# IEEE-802_15_4.net
KiCad netlist of a schematic drawn in Altium Designer
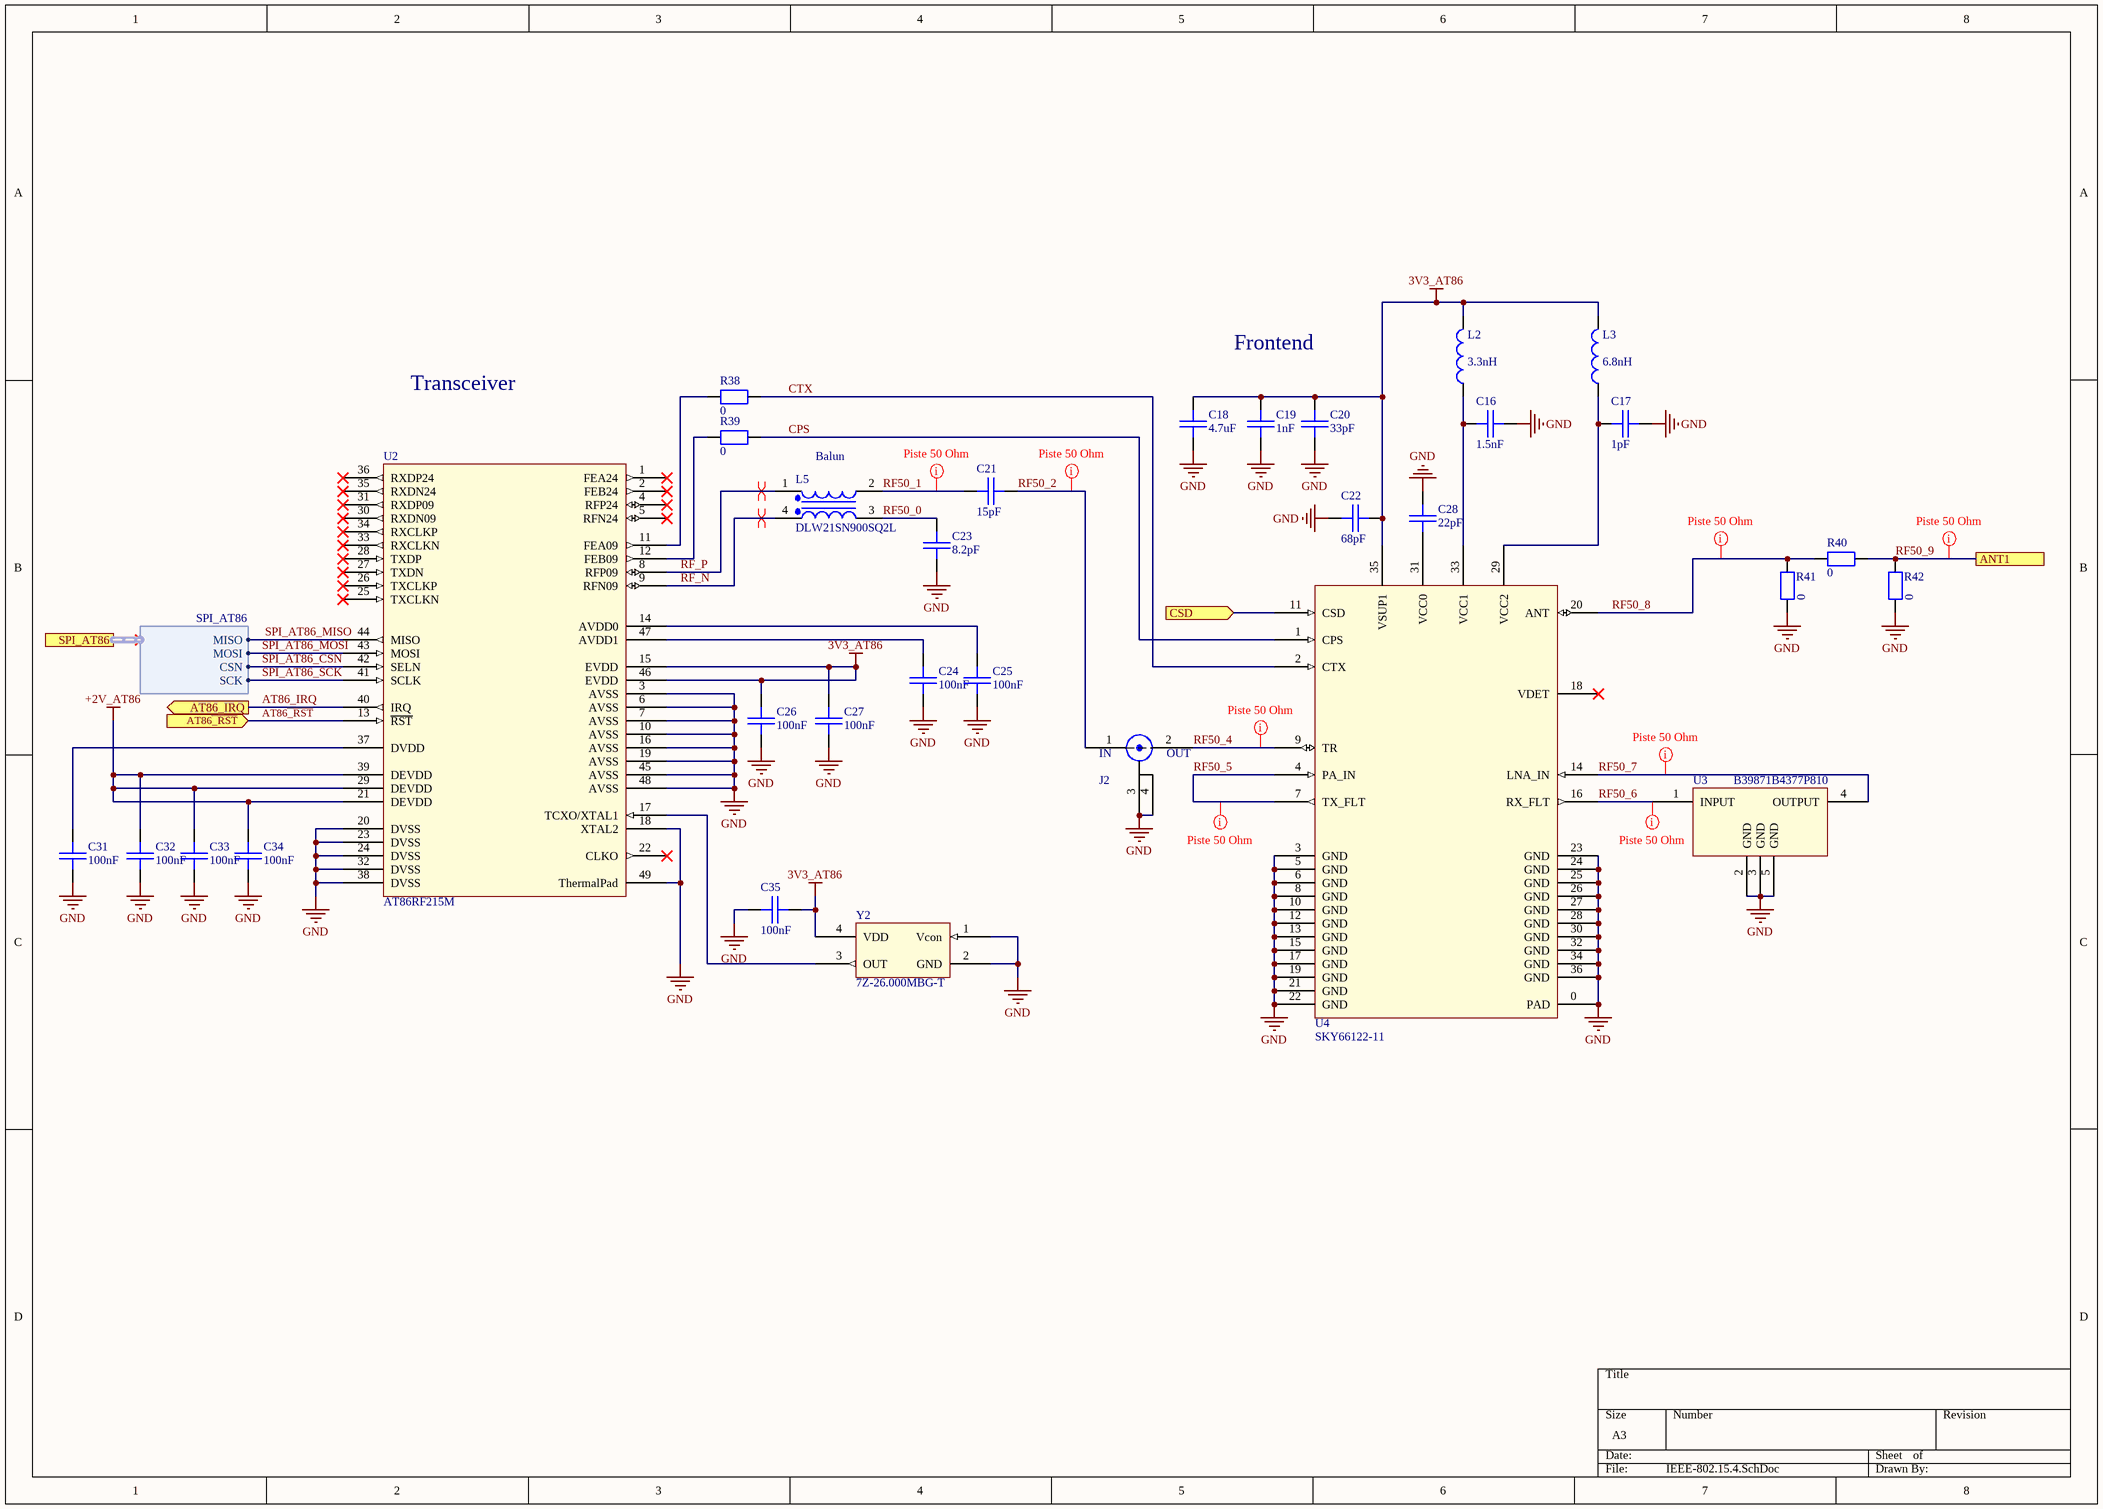
[diagram p0: IEEE-802.15.4.SchDoc]

(export (version "E")
  (design (tool "Eeschema 10.0.6"))
  (components
    (comp (ref "C16")
      (value "1.5nF")
      (footprint "SM/C_0402")
      (fields (field (name "Comment") "C-1nF-0402"))
      (libsource (lib "IEEE-802.15.4") (part "C-1.5nF-0402"))
    )
    (comp (ref "C17")
      (value "1pF")
      (footprint "SM/C_0402")
      (fields (field (name "Comment") "C-1pF-0402"))
      (libsource (lib "IEEE-802.15.4") (part "C-1pF-0402"))
    )
    (comp (ref "C18")
      (value "4.7uF")
      (footprint "SM/C_0603")
      (fields
        (field (name "VOLTAGE") "6.3V")
        (field (name "TOLERANCE") "10%")
        (field (name "Comment") "C-4.7uF-0603")
      )
      (libsource (lib "IEEE-802.15.4") (part "C-4.7uF-0603"))
    )
    (comp (ref "C19")
      (value "1nF")
      (footprint "SM/C_0402")
      (fields
        (field (name "VOLTAGE") "50V")
        (field (name "TOLERANCE") "1%")
        (field (name "Comment") "C-1nF-0402")
      )
      (libsource (lib "IEEE-802.15.4") (part "C-1nF-0402"))
    )
    (comp (ref "C20")
      (value "33pF")
      (footprint "SM/C_0402")
      (fields
        (field (name "VOLTAGE") "50V")
        (field (name "TOLERANCE") "5%")
        (field (name "Comment") "C-33pF-0402")
      )
      (libsource (lib "IEEE-802.15.4") (part "C-33pF-0402"))
    )
    (comp (ref "C21")
      (value "15pF")
      (footprint "TB_Module_RF_OFDM:SM/C_0402")
      (fields
        (field (name "VOLTAGE") "6.3V")
        (field (name "TOLERANCE") "10%")
        (field (name "Comment") "C-15pF-0402")
      )
      (libsource (lib "TB_Module_RF_OFDM") (part "C-15pF-0402"))
    )
    (comp (ref "C22")
      (value "68pF")
      (footprint "SM/C_0402")
      (fields
        (field (name "VOLTAGE") "50V")
        (field (name "TOLERANCE") "5%")
        (field (name "Comment") "C-68pF-0402")
      )
      (libsource (lib "IEEE-802.15.4") (part "C-68pF-0402"))
    )
    (comp (ref "C23")
      (value "8.2pF")
      (footprint "TB_Module_RF_OFDM:SM/C_0402")
      (fields
        (field (name "VOLTAGE") "6.3V")
        (field (name "TOLERANCE") "10%")
        (field (name "Comment") "C-8.2pF-0402")
      )
      (libsource (lib "TB_Module_RF_OFDM") (part "C-8.2pF-0402"))
    )
    (comp (ref "C24")
      (value "100nF")
      (footprint "TB_Module_RF_OFDM:SM/C_0402")
      (fields
        (field (name "VOLTAGE") "25V")
        (field (name "TOLERANCE") "10%")
        (field (name "Comment") "C-100nF-0402")
      )
      (libsource (lib "TB_Module_RF_OFDM") (part "C-100nF-0402"))
    )
    (comp (ref "C25")
      (value "100nF")
      (footprint "TB_Module_RF_OFDM:SM/C_0402")
      (fields
        (field (name "VOLTAGE") "25V")
        (field (name "TOLERANCE") "10%")
        (field (name "Comment") "C-100nF-0402")
      )
      (libsource (lib "TB_Module_RF_OFDM") (part "C-100nF-0402"))
    )
    (comp (ref "C26")
      (value "100nF")
      (footprint "TB_Module_RF_OFDM:SM/C_0402")
      (fields
        (field (name "VOLTAGE") "25V")
        (field (name "TOLERANCE") "10%")
        (field (name "Comment") "C-100nF-0402")
      )
      (libsource (lib "TB_Module_RF_OFDM") (part "C-100nF-0402"))
    )
    (comp (ref "C27")
      (value "100nF")
      (footprint "TB_Module_RF_OFDM:SM/C_0402")
      (fields
        (field (name "VOLTAGE") "25V")
        (field (name "TOLERANCE") "10%")
        (field (name "Comment") "C-100nF-0402")
      )
      (libsource (lib "TB_Module_RF_OFDM") (part "C-100nF-0402"))
    )
    (comp (ref "C28")
      (value "22pF")
      (footprint "SM/C_0402")
      (fields
        (field (name "VOLTAGE") "50V")
        (field (name "TOLERANCE") "1%")
        (field (name "Comment") "C-22pF-0402")
      )
      (libsource (lib "IEEE-802.15.4") (part "C-22pF-0402"))
    )
    (comp (ref "C31")
      (value "100nF")
      (footprint "TB_Module_RF_OFDM:SM/C_0402")
      (fields
        (field (name "VOLTAGE") "25V")
        (field (name "TOLERANCE") "10%")
        (field (name "Comment") "C-100nF-0402")
      )
      (libsource (lib "TB_Module_RF_OFDM") (part "C-100nF-0402"))
    )
    (comp (ref "C32")
      (value "100nF")
      (footprint "TB_Module_RF_OFDM:SM/C_0402")
      (fields
        (field (name "VOLTAGE") "25V")
        (field (name "TOLERANCE") "10%")
        (field (name "Comment") "C-100nF-0402")
      )
      (libsource (lib "TB_Module_RF_OFDM") (part "C-100nF-0402"))
    )
    (comp (ref "C33")
      (value "100nF")
      (footprint "TB_Module_RF_OFDM:SM/C_0402")
      (fields
        (field (name "VOLTAGE") "25V")
        (field (name "TOLERANCE") "10%")
        (field (name "Comment") "C-100nF-0402")
      )
      (libsource (lib "TB_Module_RF_OFDM") (part "C-100nF-0402"))
    )
    (comp (ref "C34")
      (value "100nF")
      (footprint "TB_Module_RF_OFDM:SM/C_0402")
      (fields
        (field (name "VOLTAGE") "25V")
        (field (name "TOLERANCE") "10%")
        (field (name "Comment") "C-100nF-0402")
      )
      (libsource (lib "TB_Module_RF_OFDM") (part "C-100nF-0402"))
    )
    (comp (ref "C35")
      (value "100nF")
      (footprint "TB_Module_RF_OFDM:SM/C_0402")
      (fields
        (field (name "VOLTAGE") "25V")
        (field (name "TOLERANCE") "10%")
        (field (name "Comment") "C-100nF-0402")
      )
      (libsource (lib "TB_Module_RF_OFDM") (part "C-100nF-0402"))
    )
    (comp (ref "J2")
      (value "MM8930-2620RJ4")
      (footprint "MM8030-2610RJ3")
      (description "SWG Connecteur Socle, prise femelle 50Ohms")
      (libsource (lib "IEEE-802.15.4") (part "MM8030-2610RJ3"))
    )
    (comp (ref "L2")
      (value "3.3nH")
      (footprint "SM/L_0402")
      (fields (field (name "TOLERANCE") "0.3nH") (field (name "Comment") "L-3.3nH-0402"))
      (libsource (lib "IEEE-802.15.4") (part "L-3.3nH-0402"))
    )
    (comp (ref "L3")
      (value "6.8nH")
      (footprint "SM/L_0603 (1608)")
      (fields (field (name "TOLERANCE") "5%") (field (name "Comment") "L-6.8nH-0603"))
      (libsource (lib "IEEE-802.15.4") (part "L-6.8nH-0603"))
    )
    (comp (ref "L5")
      (value "DLW21SN900SQ2L")
      (footprint "MURA-DLW21SN900SQ2L-4_V")
      (description "Chip Common Mode Choke Coil, 90 Ohm, 330 mA, -40 to 85 degC, 4-Pin SMD, RoHS, Tape and Reel")
      (fields (field (name "MANUFACTURER") "Murata"))
      (libsource (lib "TB_Module_RF_OFDM") (part "DLW21SN900SQ2L"))
    )
    (comp (ref "R38")
      (value "0")
      (footprint "SM/R_0402")
      (fields (field (name "TOLERANCE") "1%") (field (name "Comment") "R-0-0402"))
      (libsource (lib "TB_Module_RF_OFDM") (part "R-0-0402"))
    )
    (comp (ref "R39")
      (value "0")
      (footprint "SM/R_0402")
      (fields (field (name "TOLERANCE") "1%") (field (name "Comment") "R-0-0402"))
      (libsource (lib "TB_Module_RF_OFDM") (part "R-0-0402"))
    )
    (comp (ref "R40")
      (value "0")
      (footprint "SM/R_0402")
      (fields (field (name "TOLERANCE") "1%") (field (name "Comment") "R-0-0402"))
      (libsource (lib "TB_Module_RF_OFDM") (part "R-0-0402"))
    )
    (comp (ref "R41")
      (value "0")
      (footprint "SM/R_0402")
      (fields (field (name "TOLERANCE") "1%") (field (name "Comment") "R-0-0402"))
      (libsource (lib "TB_Module_RF_OFDM") (part "R-0-0402"))
    )
    (comp (ref "R42")
      (value "0")
      (footprint "SM/R_0402")
      (fields (field (name "TOLERANCE") "1%") (field (name "Comment") "R-0-0402"))
      (libsource (lib "TB_Module_RF_OFDM") (part "R-0-0402"))
    )
    (comp (ref "U2")
      (value "AT86RF215M")
      (footprint "QFN50P700X700X90-49N-D")
      (description "IC RF TXRX 802.15.4/ISM 48-VFQFN")
      (libsource (lib "TB_Module_RF_OFDM") (part "AT86RF215M"))
    )
    (comp (ref "U3")
      (value "B39871B4377P810")
      (footprint "B39871B4377P810")
      (libsource (lib "IEEE-802.15.4") (part "B39871B4377P810"))
    )
    (comp (ref "U4")
      (value "SKY66122-11")
      (footprint "SKY66122-11")
      (libsource (lib "IEEE-802.15.4") (part "SKY66122-11"))
    )
    (comp (ref "Y2")
      (value "7Z-26.000MBG-T")
      (footprint "TCXO")
      (description "XTAL OSC TCXO 26.0000MHZ SNWV")
      (libsource (lib "IEEE-802.15.4") (part "7Z-26.000MBG-T"))
    )
  )
  (nets
    (net (code "2") (name "+2V_AT86") (class "Default")
      (node (ref "C32") (pin "2") (pinfunction "2_2") (pintype "passive"))
      (node (ref "C33") (pin "2") (pinfunction "2_2") (pintype "passive"))
      (node (ref "C34") (pin "2") (pinfunction "2_2") (pintype "passive"))
      (node (ref "U2") (pin "21") (pinfunction "DEVDD_21") (pintype "power_in"))
      (node (ref "U2") (pin "29") (pinfunction "DEVDD_29") (pintype "power_in"))
      (node (ref "U2") (pin "39") (pinfunction "DEVDD_39") (pintype "power_in"))
    )
    (net (code "3") (name "/AT86_IRQ") (class "Default")
      (node (ref "U2") (pin "40") (pinfunction "IRQ_40") (pintype "output"))
    )
    (net (code "4") (name "/AT86~{_RST}") (class "Default")
      (node (ref "U2") (pin "13") (pinfunction "~{RST}_13") (pintype "input"))
    )
    (net (code "5") (name "/CPS") (class "Default")
      (node (ref "R39") (pin "2") (pinfunction "2_2") (pintype "passive"))
      (node (ref "U4") (pin "1") (pinfunction "CPS_1") (pintype "input"))
    )
    (net (code "6") (name "/CSD") (class "Default")
      (node (ref "U4") (pin "11") (pinfunction "CSD_11") (pintype "input"))
    )
    (net (code "7") (name "/CTX") (class "Default")
      (node (ref "R38") (pin "2") (pinfunction "2_2") (pintype "passive"))
      (node (ref "U4") (pin "2") (pinfunction "CTX_2") (pintype "input"))
    )
    (net (code "8") (name "/RF50_0") (class "Default")
      (node (ref "C23") (pin "2") (pinfunction "2_2") (pintype "passive"))
      (node (ref "L5") (pin "3") (pinfunction "3_3") (pintype "passive"))
    )
    (net (code "9") (name "/RF50_1") (class "Default")
      (node (ref "C21") (pin "1") (pinfunction "1_1") (pintype "passive"))
      (node (ref "L5") (pin "2") (pinfunction "2_2") (pintype "passive"))
    )
    (net (code "10") (name "/RF50_2") (class "Default")
      (node (ref "C21") (pin "2") (pinfunction "2_2") (pintype "passive"))
      (node (ref "J2") (pin "1") (pinfunction "IN_1") (pintype "passive"))
    )
    (net (code "11") (name "/RF50_4") (class "Default")
      (node (ref "J2") (pin "2") (pinfunction "IN_2") (pintype "passive"))
      (node (ref "U4") (pin "9") (pinfunction "TR_9") (pintype "bidirectional"))
    )
    (net (code "12") (name "/RF50_5") (class "Default")
      (node (ref "U4") (pin "4") (pinfunction "PA_IN_4") (pintype "input"))
      (node (ref "U4") (pin "7") (pinfunction "TX_FLT_7") (pintype "output"))
    )
    (net (code "13") (name "/RF50_6") (class "Default")
      (node (ref "U3") (pin "1") (pinfunction "INPUT_1") (pintype "passive"))
      (node (ref "U4") (pin "16") (pinfunction "RX_FLT_16") (pintype "output"))
    )
    (net (code "14") (name "/RF50_7") (class "Default")
      (node (ref "U3") (pin "4") (pinfunction "OUTPUT_4") (pintype "passive"))
      (node (ref "U4") (pin "14") (pinfunction "LNA_IN_14") (pintype "input"))
    )
    (net (code "15") (name "/RF50_8") (class "Default")
      (node (ref "R40") (pin "1") (pinfunction "1_1") (pintype "passive"))
      (node (ref "R41") (pin "2") (pinfunction "2_2") (pintype "passive"))
      (node (ref "U4") (pin "20") (pinfunction "ANT_20") (pintype "bidirectional"))
    )
    (net (code "16") (name "/RF50_9") (class "Default")
      (node (ref "R40") (pin "2") (pinfunction "2_2") (pintype "passive"))
      (node (ref "R42") (pin "2") (pinfunction "2_2") (pintype "passive"))
    )
    (net (code "17") (name "/RF_N") (class "Default")
      (node (ref "L5") (pin "4") (pinfunction "4_4") (pintype "passive"))
      (node (ref "U2") (pin "9") (pinfunction "RFN09_9") (pintype "bidirectional"))
    )
    (net (code "18") (name "/RF_P") (class "Default")
      (node (ref "L5") (pin "1") (pinfunction "1_1") (pintype "passive"))
      (node (ref "U2") (pin "8") (pinfunction "RFP09_8") (pintype "bidirectional"))
    )
    (net (code "19") (name "/SPI_AT86_CSN") (class "Default")
      (node (ref "U2") (pin "42") (pinfunction "SELN_42") (pintype "input"))
    )
    (net (code "20") (name "/SPI_AT86_MISO") (class "Default")
      (node (ref "U2") (pin "44") (pinfunction "MISO_44") (pintype "output"))
    )
    (net (code "21") (name "/SPI_AT86_MOSI") (class "Default")
      (node (ref "U2") (pin "43") (pinfunction "MOSI_43") (pintype "input"))
    )
    (net (code "22") (name "/SPI_AT86_SCK") (class "Default")
      (node (ref "U2") (pin "41") (pinfunction "SCLK_41") (pintype "input"))
    )
    (net (code "24") (name "3V3_AT86") (class "Default")
      (node (ref "C18") (pin "2") (pinfunction "2_2") (pintype "passive"))
      (node (ref "C19") (pin "2") (pinfunction "2_2") (pintype "passive"))
      (node (ref "C20") (pin "2") (pinfunction "2_2") (pintype "passive"))
      (node (ref "C22") (pin "2") (pinfunction "2_2") (pintype "passive"))
      (node (ref "C26") (pin "2") (pinfunction "2_2") (pintype "passive"))
      (node (ref "C27") (pin "2") (pinfunction "2_2") (pintype "passive"))
      (node (ref "C35") (pin "1") (pinfunction "1_1") (pintype "passive"))
      (node (ref "L2") (pin "2") (pinfunction "2_2") (pintype "passive"))
      (node (ref "L3") (pin "2") (pinfunction "2_2") (pintype "passive"))
      (node (ref "U2") (pin "15") (pinfunction "EVDD_15") (pintype "power_in"))
      (node (ref "U2") (pin "46") (pinfunction "EVDD_46") (pintype "power_in"))
      (node (ref "U4") (pin "35") (pinfunction "VSUP1_35") (pintype "power_in"))
      (node (ref "Y2") (pin "4") (pinfunction "VDD_4") (pintype "power_in"))
    )
    (net (code "25") (name "GND") (class "Default")
      (node (ref "C16") (pin "2") (pinfunction "2_2") (pintype "passive"))
      (node (ref "C17") (pin "2") (pinfunction "2_2") (pintype "passive"))
      (node (ref "C18") (pin "1") (pinfunction "1_1") (pintype "passive"))
      (node (ref "C19") (pin "1") (pinfunction "1_1") (pintype "passive"))
      (node (ref "C20") (pin "1") (pinfunction "1_1") (pintype "passive"))
      (node (ref "C22") (pin "1") (pinfunction "1_1") (pintype "passive"))
      (node (ref "C23") (pin "1") (pinfunction "1_1") (pintype "passive"))
      (node (ref "C24") (pin "1") (pinfunction "1_1") (pintype "passive"))
      (node (ref "C25") (pin "1") (pinfunction "1_1") (pintype "passive"))
      (node (ref "C26") (pin "1") (pinfunction "1_1") (pintype "passive"))
      (node (ref "C27") (pin "1") (pinfunction "1_1") (pintype "passive"))
      (node (ref "C28") (pin "2") (pinfunction "2_2") (pintype "passive"))
      (node (ref "C31") (pin "1") (pinfunction "1_1") (pintype "passive"))
      (node (ref "C32") (pin "1") (pinfunction "1_1") (pintype "passive"))
      (node (ref "C33") (pin "1") (pinfunction "1_1") (pintype "passive"))
      (node (ref "C34") (pin "1") (pinfunction "1_1") (pintype "passive"))
      (node (ref "C35") (pin "2") (pinfunction "2_2") (pintype "passive"))
      (node (ref "J2") (pin "3") (pinfunction "GND_3") (pintype "passive"))
      (node (ref "J2") (pin "4") (pinfunction "GND_4") (pintype "passive"))
      (node (ref "R41") (pin "1") (pinfunction "1_1") (pintype "passive"))
      (node (ref "R42") (pin "1") (pinfunction "1_1") (pintype "passive"))
      (node (ref "U2") (pin "10") (pinfunction "AVSS_10") (pintype "power_in"))
      (node (ref "U2") (pin "16") (pinfunction "AVSS_16") (pintype "power_in"))
      (node (ref "U2") (pin "18") (pinfunction "XTAL2_18") (pintype "passive"))
      (node (ref "U2") (pin "19") (pinfunction "AVSS_19") (pintype "power_in"))
      (node (ref "U2") (pin "20") (pinfunction "DVSS_20") (pintype "power_in"))
      (node (ref "U2") (pin "23") (pinfunction "DVSS_23") (pintype "power_in"))
      (node (ref "U2") (pin "24") (pinfunction "DVSS_24") (pintype "power_in"))
      (node (ref "U2") (pin "3") (pinfunction "AVSS_3") (pintype "power_in"))
      (node (ref "U2") (pin "32") (pinfunction "DVSS_32") (pintype "power_in"))
      (node (ref "U2") (pin "38") (pinfunction "DVSS_38") (pintype "power_in"))
      (node (ref "U2") (pin "45") (pinfunction "AVSS_45") (pintype "power_in"))
      (node (ref "U2") (pin "48") (pinfunction "AVSS_48") (pintype "power_in"))
      (node (ref "U2") (pin "49") (pinfunction "ThermalPad_49") (pintype "passive"))
      (node (ref "U2") (pin "6") (pinfunction "AVSS_6") (pintype "power_in"))
      (node (ref "U2") (pin "7") (pinfunction "AVSS_7") (pintype "power_in"))
      (node (ref "U3") (pin "2") (pinfunction "GND_2") (pintype "passive"))
      (node (ref "U3") (pin "3") (pinfunction "GND_3") (pintype "passive"))
      (node (ref "U3") (pin "5") (pinfunction "GND_5") (pintype "passive"))
      (node (ref "U4") (pin "0") (pinfunction "PAD_0") (pintype "power_in"))
      (node (ref "U4") (pin "10") (pinfunction "GND_10") (pintype "passive"))
      (node (ref "U4") (pin "12") (pinfunction "GND_12") (pintype "passive"))
      (node (ref "U4") (pin "13") (pinfunction "GND_13") (pintype "passive"))
      (node (ref "U4") (pin "15") (pinfunction "GND_15") (pintype "passive"))
      (node (ref "U4") (pin "17") (pinfunction "GND_17") (pintype "passive"))
      (node (ref "U4") (pin "19") (pinfunction "GND_19") (pintype "passive"))
      (node (ref "U4") (pin "21") (pinfunction "GND_21") (pintype "passive"))
      (node (ref "U4") (pin "22") (pinfunction "GND_22") (pintype "power_in"))
      (node (ref "U4") (pin "23") (pinfunction "GND_23") (pintype "power_in"))
      (node (ref "U4") (pin "24") (pinfunction "GND_24") (pintype "power_in"))
      (node (ref "U4") (pin "25") (pinfunction "GND_25") (pintype "power_in"))
      (node (ref "U4") (pin "26") (pinfunction "GND_26") (pintype "power_in"))
      (node (ref "U4") (pin "27") (pinfunction "GND_27") (pintype "power_in"))
      (node (ref "U4") (pin "28") (pinfunction "GND_28") (pintype "power_in"))
      (node (ref "U4") (pin "3") (pinfunction "GND_3") (pintype "power_in"))
      (node (ref "U4") (pin "30") (pinfunction "GND_30") (pintype "power_in"))
      (node (ref "U4") (pin "32") (pinfunction "GND_32") (pintype "power_in"))
      (node (ref "U4") (pin "34") (pinfunction "GND_34") (pintype "power_in"))
      (node (ref "U4") (pin "36") (pinfunction "GND_36") (pintype "power_in"))
      (node (ref "U4") (pin "5") (pinfunction "GND_5") (pintype "power_in"))
      (node (ref "U4") (pin "6") (pinfunction "GND_6") (pintype "power_in"))
      (node (ref "U4") (pin "8") (pinfunction "GND_8") (pintype "power_in"))
      (node (ref "Y2") (pin "1") (pinfunction "Vcon_1") (pintype "input"))
      (node (ref "Y2") (pin "2") (pinfunction "GND_2") (pintype "power_in"))
    )
    (net (code "26") (name "Net-(U2-AVDD0)") (class "Default")
      (node (ref "C25") (pin "2") (pinfunction "2_2") (pintype "passive"))
      (node (ref "U2") (pin "14") (pinfunction "AVDD0_14") (pintype "power_in"))
    )
    (net (code "27") (name "Net-(U2-AVDD1)") (class "Default")
      (node (ref "C24") (pin "2") (pinfunction "2_2") (pintype "passive"))
      (node (ref "U2") (pin "47") (pinfunction "AVDD1_47") (pintype "power_in"))
    )
    (net (code "28") (name "Net-(U2-DVDD)") (class "Default")
      (node (ref "C31") (pin "2") (pinfunction "2_2") (pintype "passive"))
      (node (ref "U2") (pin "37") (pinfunction "DVDD_37") (pintype "power_in"))
    )
    (net (code "29") (name "Net-(U2-FEA09)") (class "Default")
      (node (ref "R38") (pin "1") (pinfunction "1_1") (pintype "passive"))
      (node (ref "U2") (pin "11") (pinfunction "FEA09_11") (pintype "output"))
    )
    (net (code "30") (name "Net-(U2-FEB09)") (class "Default")
      (node (ref "R39") (pin "1") (pinfunction "1_1") (pintype "passive"))
      (node (ref "U2") (pin "12") (pinfunction "FEB09_12") (pintype "output"))
    )
    (net (code "31") (name "Net-(U2-TCXO{slash}XTAL1)") (class "Default")
      (node (ref "U2") (pin "17") (pinfunction "TCXO/XTAL1_17") (pintype "input"))
      (node (ref "Y2") (pin "3") (pinfunction "OUT_3") (pintype "output"))
    )
    (net (code "32") (name "Net-(U4-VCC0)") (class "Default")
      (node (ref "C28") (pin "1") (pinfunction "1_1") (pintype "passive"))
      (node (ref "U4") (pin "31") (pinfunction "VCC0_31") (pintype "power_in"))
    )
    (net (code "33") (name "Net-(U4-VCC1)") (class "Default")
      (node (ref "C16") (pin "1") (pinfunction "1_1") (pintype "passive"))
      (node (ref "L2") (pin "1") (pinfunction "1_1") (pintype "passive"))
      (node (ref "U4") (pin "33") (pinfunction "VCC1_33") (pintype "power_in"))
    )
    (net (code "34") (name "Net-(U4-VCC2)") (class "Default")
      (node (ref "C17") (pin "1") (pinfunction "1_1") (pintype "passive"))
      (node (ref "L3") (pin "1") (pinfunction "1_1") (pintype "passive"))
      (node (ref "U4") (pin "29") (pinfunction "VCC2_29") (pintype "power_in"))
    )
    (net (code "35") (name "unconnected-(U2-CLKO-Pad22)") (class "Default")
      (node (ref "U2") (pin "22") (pinfunction "CLKO_22") (pintype "output+no_connect"))
    )
    (net (code "36") (name "unconnected-(U2-FEA24-Pad1)") (class "Default")
      (node (ref "U2") (pin "1") (pinfunction "FEA24_1") (pintype "output+no_connect"))
    )
    (net (code "37") (name "unconnected-(U2-FEB24-Pad2)") (class "Default")
      (node (ref "U2") (pin "2") (pinfunction "FEB24_2") (pintype "output+no_connect"))
    )
    (net (code "38") (name "unconnected-(U2-RFN24-Pad5)") (class "Default")
      (node (ref "U2") (pin "5") (pinfunction "RFN24_5") (pintype "bidirectional+no_connect"))
    )
    (net (code "39") (name "unconnected-(U2-RFP24-Pad4)") (class "Default")
      (node (ref "U2") (pin "4") (pinfunction "RFP24_4") (pintype "bidirectional+no_connect"))
    )
    (net (code "40") (name "unconnected-(U2-RXCLKN-Pad33)") (class "Default")
      (node (ref "U2") (pin "33") (pinfunction "RXCLKN_33") (pintype "output+no_connect"))
    )
    (net (code "41") (name "unconnected-(U2-RXCLKP-Pad34)") (class "Default")
      (node (ref "U2") (pin "34") (pinfunction "RXCLKP_34") (pintype "output+no_connect"))
    )
    (net (code "42") (name "unconnected-(U2-RXDN09-Pad30)") (class "Default")
      (node (ref "U2") (pin "30") (pinfunction "RXDN09_30") (pintype "output+no_connect"))
    )
    (net (code "43") (name "unconnected-(U2-RXDN24-Pad35)") (class "Default")
      (node (ref "U2") (pin "35") (pinfunction "RXDN24_35") (pintype "output+no_connect"))
    )
    (net (code "44") (name "unconnected-(U2-RXDP09-Pad31)") (class "Default")
      (node (ref "U2") (pin "31") (pinfunction "RXDP09_31") (pintype "output+no_connect"))
    )
    (net (code "45") (name "unconnected-(U2-RXDP24-Pad36)") (class "Default")
      (node (ref "U2") (pin "36") (pinfunction "RXDP24_36") (pintype "output+no_connect"))
    )
    (net (code "46") (name "unconnected-(U2-TXCLKN-Pad25)") (class "Default")
      (node (ref "U2") (pin "25") (pinfunction "TXCLKN_25") (pintype "input+no_connect"))
    )
    (net (code "47") (name "unconnected-(U2-TXCLKP-Pad26)") (class "Default")
      (node (ref "U2") (pin "26") (pinfunction "TXCLKP_26") (pintype "input+no_connect"))
    )
    (net (code "48") (name "unconnected-(U2-TXDN-Pad27)") (class "Default")
      (node (ref "U2") (pin "27") (pinfunction "TXDN_27") (pintype "input+no_connect"))
    )
    (net (code "49") (name "unconnected-(U2-TXDP-Pad28)") (class "Default")
      (node (ref "U2") (pin "28") (pinfunction "TXDP_28") (pintype "input+no_connect"))
    )
    (net (code "50") (name "unconnected-(U4-VDET-Pad18)") (class "Default")
      (node (ref "U4") (pin "18") (pinfunction "VDET_18") (pintype "power_in+no_connect"))
    )
  )
)
